# SX1276_e268v01a.net
KiCad netlist of a schematic drawn in Altium Designer
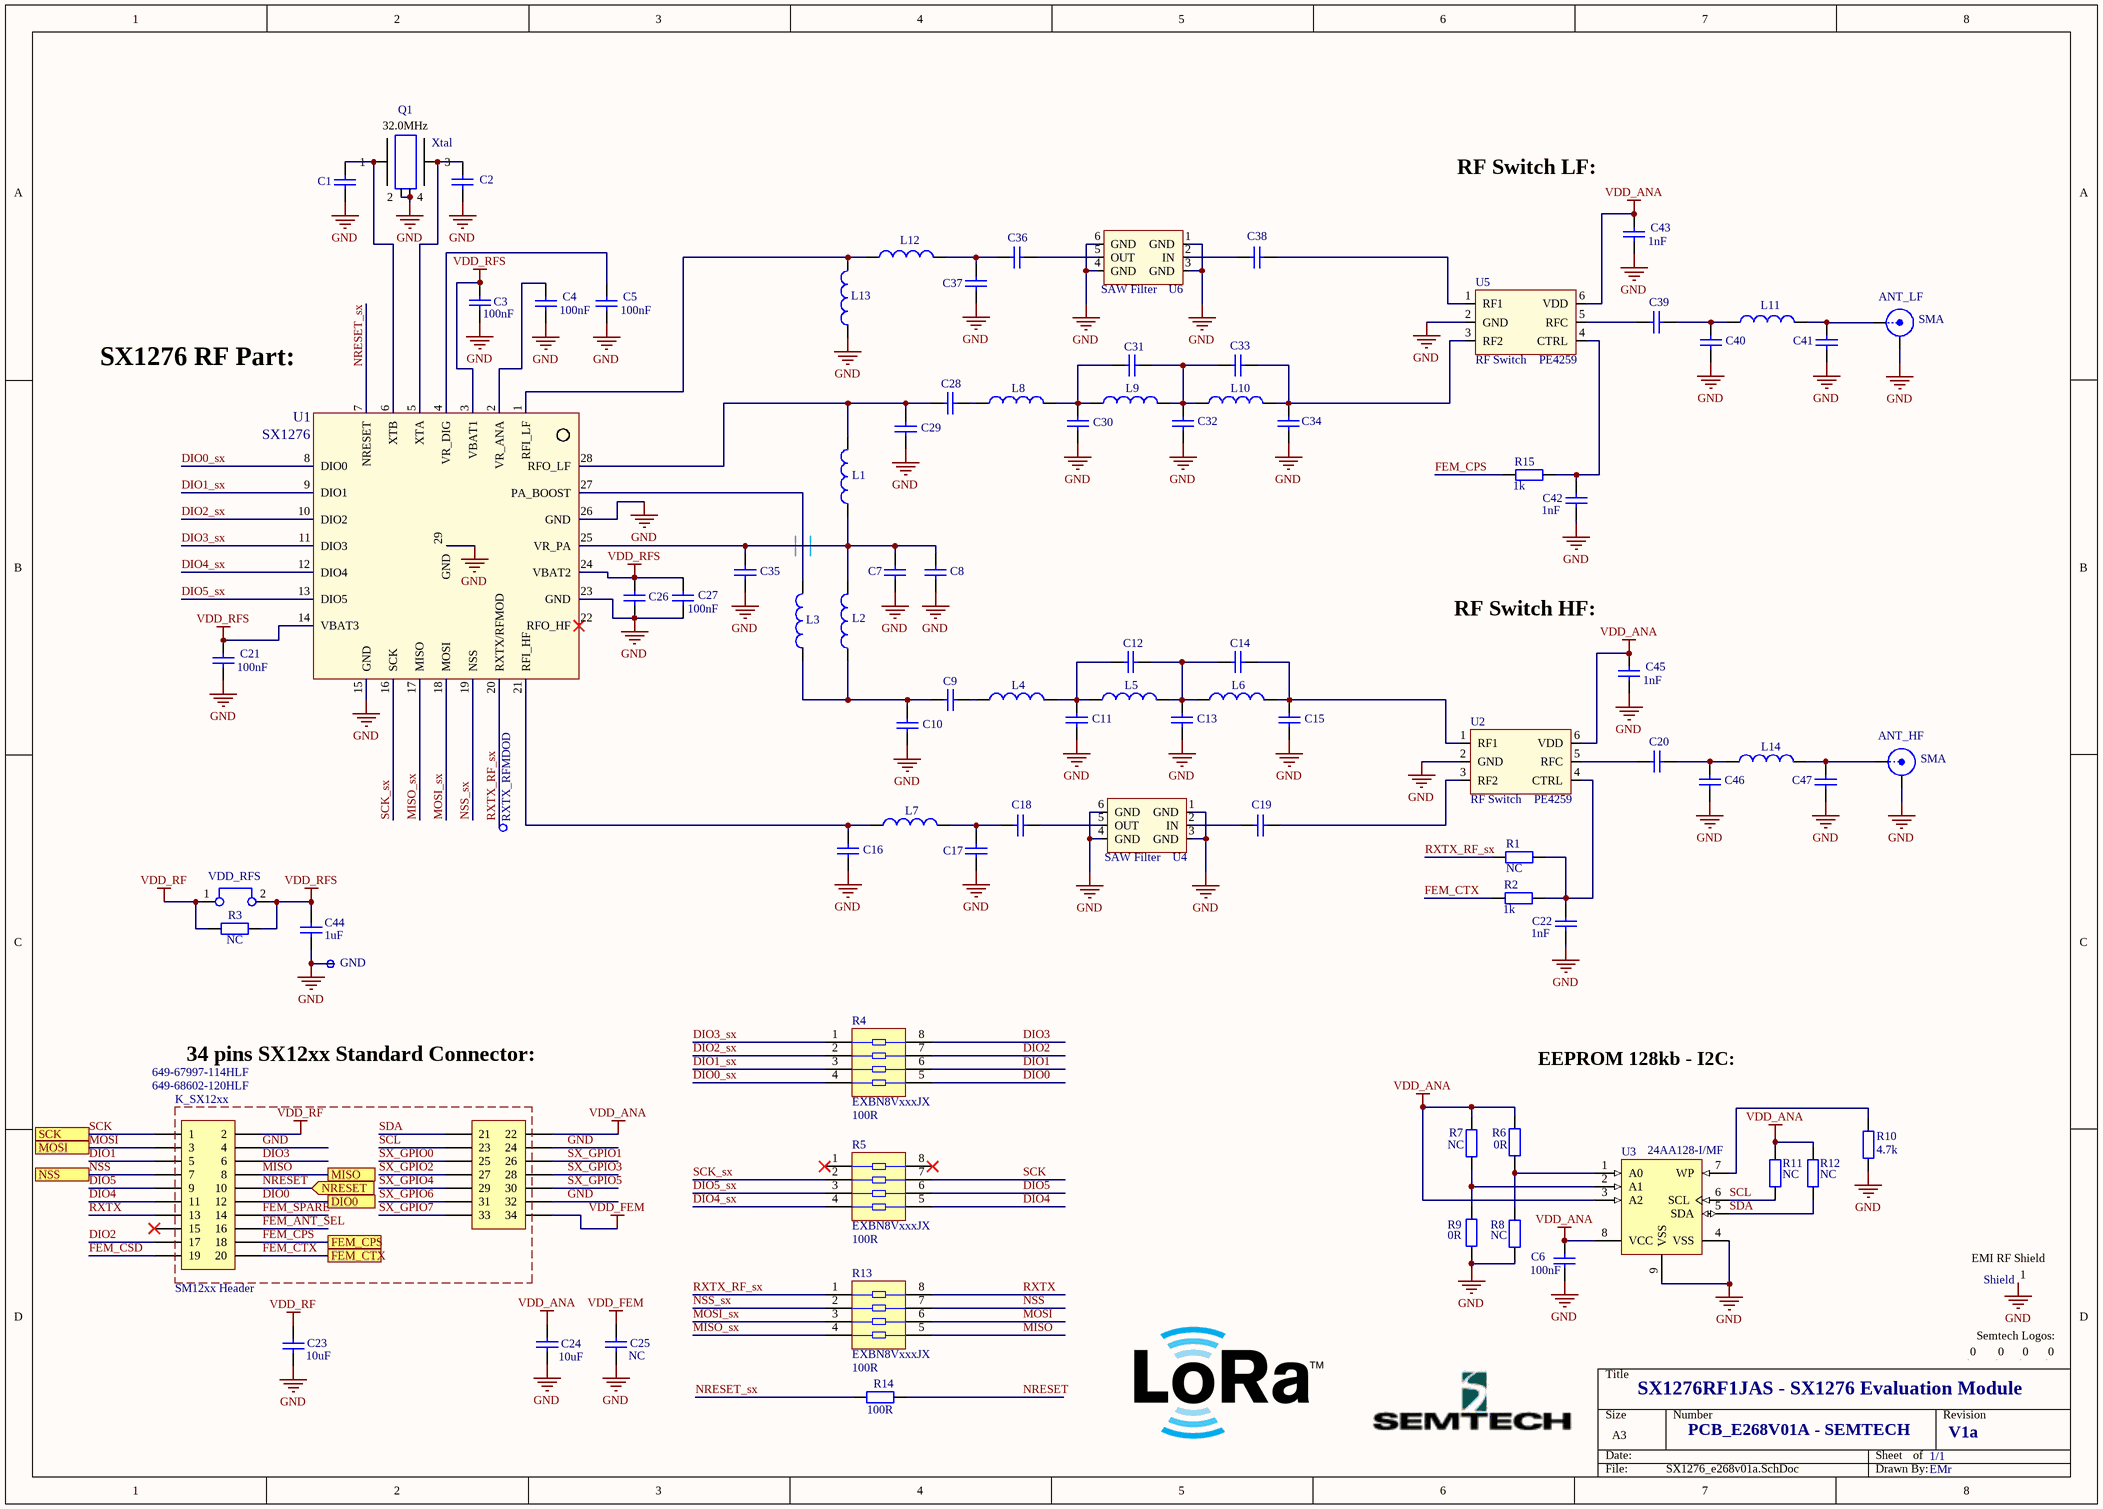
[diagram p0: SX1276_e268v01a.SchDoc]

(export (version "E")
  (design (tool "Eeschema 10.0.6"))
  (components
    (comp (ref "ANT_HF")
      (value "SMA")
      (footprint "SMA END LAUNCH JACK RECEPTACLE SHORT")
      (description "SMA Straight Connector")
      (fields (field (name "PUBLISHER") "Altium Limited"))
      (libsource (lib "SX1276_e268v01a") (part "SMA"))
    )
    (comp (ref "ANT_LF")
      (value "SMA")
      (footprint "SMA END LAUNCH JACK RECEPTACLE SHORT")
      (description "SMA Straight Connector")
      (fields (field (name "PUBLISHER") "Altium Limited"))
      (libsource (lib "SX1276_e268v01a") (part "SMA"))
    )
    (comp (ref "C1")
      (value "Cap")
      (footprint "rlc_402_smd")
      (description "Capacitor SMD")
      (fields (field (name "PUBLISHER") "Altium Limited"))
      (libsource (lib "SX1276_e268v01a") (part "Cap"))
    )
    (comp (ref "C2")
      (value "Cap")
      (footprint "rlc_402_smd")
      (description "Capacitor SMD")
      (fields (field (name "PUBLISHER") "Altium Limited"))
      (libsource (lib "SX1276_e268v01a") (part "Cap"))
    )
    (comp (ref "C3")
      (value "100nF")
      (footprint "rlc_402_smd")
      (description "Capacitor SMD")
      (fields (field (name "Comment") "Cap") (field (name "PUBLISHER") "Altium Limited"))
      (libsource (lib "SX1276_e268v01a") (part "Cap"))
    )
    (comp (ref "C4")
      (value "100nF")
      (footprint "rlc_402_smd")
      (description "Capacitor SMD")
      (fields (field (name "Comment") "Cap") (field (name "PUBLISHER") "Altium Limited"))
      (libsource (lib "SX1276_e268v01a") (part "Cap"))
    )
    (comp (ref "C5")
      (value "100nF")
      (footprint "rlc_402_smd")
      (description "Capacitor SMD")
      (fields (field (name "Comment") "Cap") (field (name "PUBLISHER") "Altium Limited"))
      (libsource (lib "SX1276_e268v01a") (part "Cap"))
    )
    (comp (ref "C6")
      (value "100nF")
      (footprint "rlc_402_smd")
      (description "Capacitor SMD")
      (fields (field (name "Comment") "Cap") (field (name "PUBLISHER") "Altium Limited"))
      (libsource (lib "SX1276_e268v01a") (part "Cap"))
    )
    (comp (ref "C7")
      (value "Cap")
      (footprint "rlc_402_smd")
      (description "Capacitor SMD")
      (fields (field (name "PUBLISHER") "Altium Limited"))
      (libsource (lib "SX1276_e268v01a") (part "Cap"))
    )
    (comp (ref "C8")
      (value "Cap")
      (footprint "rlc_402_smd")
      (description "Capacitor SMD")
      (fields (field (name "PUBLISHER") "Altium Limited"))
      (libsource (lib "SX1276_e268v01a") (part "Cap"))
    )
    (comp (ref "C9")
      (value "Cap")
      (footprint "rlc_402_smd")
      (description "Capacitor SMD")
      (fields (field (name "PUBLISHER") "Altium Limited"))
      (libsource (lib "SX1276_e268v01a") (part "Cap"))
    )
    (comp (ref "C10")
      (value "Cap")
      (footprint "rlc_402_smd")
      (description "Capacitor SMD")
      (fields (field (name "PUBLISHER") "Altium Limited"))
      (libsource (lib "SX1276_e268v01a") (part "Cap"))
    )
    (comp (ref "C11")
      (value "Cap")
      (footprint "rlc_402_smd")
      (description "Capacitor SMD")
      (fields (field (name "PUBLISHER") "Altium Limited"))
      (libsource (lib "SX1276_e268v01a") (part "Cap"))
    )
    (comp (ref "C12")
      (value "Cap")
      (footprint "rlc_402_smd")
      (description "Capacitor SMD")
      (fields (field (name "PUBLISHER") "Altium Limited"))
      (libsource (lib "SX1276_e268v01a") (part "Cap"))
    )
    (comp (ref "C13")
      (value "Cap")
      (footprint "rlc_402_smd")
      (description "Capacitor SMD")
      (fields (field (name "PUBLISHER") "Altium Limited"))
      (libsource (lib "SX1276_e268v01a") (part "Cap"))
    )
    (comp (ref "C14")
      (value "Cap")
      (footprint "rlc_402_smd")
      (description "Capacitor SMD")
      (fields (field (name "PUBLISHER") "Altium Limited"))
      (libsource (lib "SX1276_e268v01a") (part "Cap"))
    )
    (comp (ref "C15")
      (value "Cap")
      (footprint "rlc_402_smd")
      (description "Capacitor SMD")
      (fields (field (name "PUBLISHER") "Altium Limited"))
      (libsource (lib "SX1276_e268v01a") (part "Cap"))
    )
    (comp (ref "C16")
      (value "Cap")
      (footprint "rlc_402_smd")
      (description "Capacitor SMD")
      (fields (field (name "PUBLISHER") "Altium Limited"))
      (libsource (lib "SX1276_e268v01a") (part "Cap"))
    )
    (comp (ref "C17")
      (value "Cap")
      (footprint "rlc_402_smd")
      (description "Capacitor SMD")
      (fields (field (name "PUBLISHER") "Altium Limited"))
      (libsource (lib "SX1276_e268v01a") (part "Cap"))
    )
    (comp (ref "C18")
      (value "Cap")
      (footprint "rlc_402_smd")
      (description "Capacitor SMD")
      (fields (field (name "PUBLISHER") "Altium Limited"))
      (libsource (lib "SX1276_e268v01a") (part "Cap"))
    )
    (comp (ref "C19")
      (value "Cap")
      (footprint "rlc_402_smd")
      (description "Capacitor SMD")
      (fields (field (name "PUBLISHER") "Altium Limited"))
      (libsource (lib "SX1276_e268v01a") (part "Cap"))
    )
    (comp (ref "C20")
      (value "Cap")
      (footprint "rlc_402_smd")
      (description "Capacitor SMD")
      (fields (field (name "PUBLISHER") "Altium Limited"))
      (libsource (lib "SX1276_e268v01a") (part "Cap"))
    )
    (comp (ref "C21")
      (value "100nF")
      (footprint "rlc_402_smd")
      (description "Capacitor SMD")
      (fields (field (name "Comment") "Cap") (field (name "PUBLISHER") "Altium Limited"))
      (libsource (lib "SX1276_e268v01a") (part "Cap"))
    )
    (comp (ref "C22")
      (value "1nF")
      (footprint "rlc_402_smd")
      (description "Capacitor SMD")
      (fields (field (name "Comment") "Cap") (field (name "PUBLISHER") "Altium Limited"))
      (libsource (lib "SX1276_e268v01a") (part "Cap"))
    )
    (comp (ref "C23")
      (value "10uF")
      (footprint "rlc_805_smd")
      (description "Capacitor SMD")
      (fields (field (name "Comment") "Cap") (field (name "PUBLISHER") "Altium Limited"))
      (libsource (lib "SX1276_e268v01a") (part "Cap"))
    )
    (comp (ref "C24")
      (value "10uF")
      (footprint "rlc_805_smd")
      (description "Capacitor SMD")
      (fields (field (name "Comment") "Cap") (field (name "PUBLISHER") "Altium Limited"))
      (libsource (lib "SX1276_e268v01a") (part "Cap"))
    )
    (comp (ref "C25")
      (value "NC")
      (footprint "rlc_805_smd")
      (description "Capacitor SMD")
      (fields (field (name "Comment") "Cap") (field (name "PUBLISHER") "Altium Limited"))
      (libsource (lib "SX1276_e268v01a") (part "Cap"))
    )
    (comp (ref "C26")
      (value "Cap")
      (footprint "rlc_402_smd")
      (description "Capacitor SMD")
      (fields (field (name "PUBLISHER") "Altium Limited"))
      (libsource (lib "SX1276_e268v01a") (part "Cap"))
    )
    (comp (ref "C27")
      (value "100nF")
      (footprint "rlc_402_smd")
      (description "Capacitor SMD")
      (fields (field (name "Comment") "Cap") (field (name "PUBLISHER") "Altium Limited"))
      (libsource (lib "SX1276_e268v01a") (part "Cap"))
    )
    (comp (ref "C28")
      (value "Cap")
      (footprint "rlc_402_smd")
      (description "Capacitor SMD")
      (fields (field (name "PUBLISHER") "Altium Limited"))
      (libsource (lib "SX1276_e268v01a") (part "Cap"))
    )
    (comp (ref "C29")
      (value "Cap")
      (footprint "rlc_402_smd")
      (description "Capacitor SMD")
      (fields (field (name "PUBLISHER") "Altium Limited"))
      (libsource (lib "SX1276_e268v01a") (part "Cap"))
    )
    (comp (ref "C30")
      (value "Cap")
      (footprint "rlc_402_smd")
      (description "Capacitor SMD")
      (fields (field (name "PUBLISHER") "Altium Limited"))
      (libsource (lib "SX1276_e268v01a") (part "Cap"))
    )
    (comp (ref "C31")
      (value "Cap")
      (footprint "rlc_402_smd")
      (description "Capacitor SMD")
      (fields (field (name "PUBLISHER") "Altium Limited"))
      (libsource (lib "SX1276_e268v01a") (part "Cap"))
    )
    (comp (ref "C32")
      (value "Cap")
      (footprint "rlc_402_smd")
      (description "Capacitor SMD")
      (fields (field (name "PUBLISHER") "Altium Limited"))
      (libsource (lib "SX1276_e268v01a") (part "Cap"))
    )
    (comp (ref "C33")
      (value "Cap")
      (footprint "rlc_402_smd")
      (description "Capacitor SMD")
      (fields (field (name "PUBLISHER") "Altium Limited"))
      (libsource (lib "SX1276_e268v01a") (part "Cap"))
    )
    (comp (ref "C34")
      (value "Cap")
      (footprint "rlc_402_smd")
      (description "Capacitor SMD")
      (fields (field (name "PUBLISHER") "Altium Limited"))
      (libsource (lib "SX1276_e268v01a") (part "Cap"))
    )
    (comp (ref "C35")
      (value "Cap")
      (footprint "rlc_402_smd")
      (description "Capacitor SMD")
      (fields (field (name "PUBLISHER") "Altium Limited"))
      (libsource (lib "SX1276_e268v01a") (part "Cap"))
    )
    (comp (ref "C36")
      (value "Cap")
      (footprint "rlc_402_smd")
      (description "Capacitor SMD")
      (fields (field (name "PUBLISHER") "Altium Limited"))
      (libsource (lib "SX1276_e268v01a") (part "Cap"))
    )
    (comp (ref "C37")
      (value "Cap")
      (footprint "rlc_402_smd")
      (description "Capacitor SMD")
      (fields (field (name "PUBLISHER") "Altium Limited"))
      (libsource (lib "SX1276_e268v01a") (part "Cap"))
    )
    (comp (ref "C38")
      (value "Cap")
      (footprint "rlc_402_smd")
      (description "Capacitor SMD")
      (fields (field (name "PUBLISHER") "Altium Limited"))
      (libsource (lib "SX1276_e268v01a") (part "Cap"))
    )
    (comp (ref "C39")
      (value "Cap")
      (footprint "rlc_402_smd")
      (description "Capacitor SMD")
      (fields (field (name "PUBLISHER") "Altium Limited"))
      (libsource (lib "SX1276_e268v01a") (part "Cap"))
    )
    (comp (ref "C40")
      (value "Cap")
      (footprint "rlc_402_smd")
      (description "Capacitor SMD")
      (fields (field (name "PUBLISHER") "Altium Limited"))
      (libsource (lib "SX1276_e268v01a") (part "Cap"))
    )
    (comp (ref "C41")
      (value "Cap")
      (footprint "rlc_402_smd")
      (description "Capacitor SMD")
      (fields (field (name "PUBLISHER") "Altium Limited"))
      (libsource (lib "SX1276_e268v01a") (part "Cap"))
    )
    (comp (ref "C42")
      (value "1nF")
      (footprint "rlc_402_smd")
      (description "Capacitor SMD")
      (fields (field (name "Comment") "Cap") (field (name "PUBLISHER") "Altium Limited"))
      (libsource (lib "SX1276_e268v01a") (part "Cap"))
    )
    (comp (ref "C43")
      (value "1nF")
      (footprint "rlc_402_smd")
      (description "Capacitor SMD")
      (fields (field (name "Comment") "Cap") (field (name "PUBLISHER") "Altium Limited"))
      (libsource (lib "SX1276_e268v01a") (part "Cap"))
    )
    (comp (ref "C44")
      (value "1uF")
      (footprint "rlc_603_smd")
      (description "Capacitor (Semiconductor SIM Model)")
      (fields (field (name "Comment") "Cap Semi") (field (name "PUBLISHER") "Altium Limited"))
      (libsource (lib "SX1276_e268v01a") (part "Cap Semi"))
    )
    (comp (ref "C45")
      (value "1nF")
      (footprint "rlc_402_smd")
      (description "Capacitor SMD")
      (fields (field (name "Comment") "Cap") (field (name "PUBLISHER") "Altium Limited"))
      (libsource (lib "SX1276_e268v01a") (part "Cap"))
    )
    (comp (ref "C46")
      (value "Cap")
      (footprint "rlc_402_smd")
      (description "Capacitor SMD")
      (fields (field (name "PUBLISHER") "Altium Limited"))
      (libsource (lib "SX1276_e268v01a") (part "Cap"))
    )
    (comp (ref "C47")
      (value "Cap")
      (footprint "rlc_402_smd")
      (description "Capacitor SMD")
      (fields (field (name "PUBLISHER") "Altium Limited"))
      (libsource (lib "SX1276_e268v01a") (part "Cap"))
    )
    (comp (ref "GND")
      (value "Test Pin")
      (footprint "pin_1mm")
      (libsource (lib "SX1276_e268v01a") (part "test_pin"))
    )
    (comp (ref "K_SX12xx")
      (value "SM12xx Header")
      (footprint "HDR34 Header")
      (description "SM12xx Header; 34pins: 2x10pins + 2x7pins")
      (fields
        (field (name "SUPPLIER PART NUMBER 1") "649-68602-120HLF")
        (field (name "SUPPLIER PART NUMBER 2") "649-67997-114HLF")
        (field (name "PUBLISHER") "Altium Limited")
      )
      (libsource (lib "SX1276_e268v01a") (part "SM12xx Header"))
    )
    (comp (ref "L1")
      (value "Inductor")
      (footprint "rlc_402_smd")
      (description "Inductor SMD")
      (fields (field (name "PUBLISHER") "Altium Limited"))
      (libsource (lib "SX1276_e268v01a") (part "Inductor"))
    )
    (comp (ref "L2")
      (value "Inductor")
      (footprint "rlc_402_smd")
      (description "Inductor SMD")
      (fields (field (name "PUBLISHER") "Altium Limited"))
      (libsource (lib "SX1276_e268v01a") (part "Inductor"))
    )
    (comp (ref "L3")
      (value "Inductor")
      (footprint "rlc_402_smd")
      (description "Inductor SMD")
      (fields (field (name "PUBLISHER") "Altium Limited"))
      (libsource (lib "SX1276_e268v01a") (part "Inductor"))
    )
    (comp (ref "L4")
      (value "Inductor")
      (footprint "rlc_402_smd")
      (description "Inductor SMD")
      (fields (field (name "PUBLISHER") "Altium Limited"))
      (libsource (lib "SX1276_e268v01a") (part "Inductor"))
    )
    (comp (ref "L5")
      (value "Inductor")
      (footprint "rlc_402_smd")
      (description "Inductor SMD")
      (fields (field (name "PUBLISHER") "Altium Limited"))
      (libsource (lib "SX1276_e268v01a") (part "Inductor"))
    )
    (comp (ref "L6")
      (value "Inductor")
      (footprint "rlc_402_smd")
      (description "Inductor SMD")
      (fields (field (name "PUBLISHER") "Altium Limited"))
      (libsource (lib "SX1276_e268v01a") (part "Inductor"))
    )
    (comp (ref "L7")
      (value "Inductor")
      (footprint "rlc_402_smd")
      (description "Inductor SMD")
      (fields (field (name "PUBLISHER") "Altium Limited"))
      (libsource (lib "SX1276_e268v01a") (part "Inductor"))
    )
    (comp (ref "L8")
      (value "Inductor")
      (footprint "rlc_402_smd")
      (description "Inductor SMD")
      (fields (field (name "PUBLISHER") "Altium Limited"))
      (libsource (lib "SX1276_e268v01a") (part "Inductor"))
    )
    (comp (ref "L9")
      (value "Inductor")
      (footprint "rlc_402_smd")
      (description "Inductor SMD")
      (fields (field (name "PUBLISHER") "Altium Limited"))
      (libsource (lib "SX1276_e268v01a") (part "Inductor"))
    )
    (comp (ref "L10")
      (value "Inductor")
      (footprint "rlc_402_smd")
      (description "Inductor SMD")
      (fields (field (name "PUBLISHER") "Altium Limited"))
      (libsource (lib "SX1276_e268v01a") (part "Inductor"))
    )
    (comp (ref "L11")
      (value "Inductor")
      (footprint "rlc_402_smd")
      (description "Inductor SMD")
      (fields (field (name "PUBLISHER") "Altium Limited"))
      (libsource (lib "SX1276_e268v01a") (part "Inductor"))
    )
    (comp (ref "L12")
      (value "Inductor")
      (footprint "rlc_402_smd")
      (description "Inductor SMD")
      (fields (field (name "PUBLISHER") "Altium Limited"))
      (libsource (lib "SX1276_e268v01a") (part "Inductor"))
    )
    (comp (ref "L13")
      (value "Inductor")
      (footprint "rlc_402_smd")
      (description "Inductor SMD")
      (fields (field (name "PUBLISHER") "Altium Limited"))
      (libsource (lib "SX1276_e268v01a") (part "Inductor"))
    )
    (comp (ref "L14")
      (value "Inductor")
      (footprint "rlc_402_smd")
      (description "Inductor SMD")
      (fields (field (name "PUBLISHER") "Altium Limited"))
      (libsource (lib "SX1276_e268v01a") (part "Inductor"))
    )
    (comp (ref "Logo Bot")
      (value "Logo symbol")
      (footprint "logo_semtech_horiz_size3")
      (description "Schematic symbol for Logo")
      (libsource (lib "SX1276_e268v01a") (part "Logo"))
    )
    (comp (ref "Logo Lora Bot")
      (value "Logo symbol")
      (footprint "Logo LoRa Size4")
      (description "Schematic symbol for Logo")
      (libsource (lib "SX1276_e268v01a") (part "Logo"))
    )
    (comp (ref "Logo Lora Top")
      (value "Logo symbol")
      (footprint "Logo LoRa Size3")
      (description "Schematic symbol for Logo")
      (libsource (lib "SX1276_e268v01a") (part "Logo"))
    )
    (comp (ref "Logo Top")
      (value "Logo symbol")
      (footprint "logo_semtech_horiz_size2")
      (description "Schematic symbol for Logo")
      (libsource (lib "SX1276_e268v01a") (part "Logo"))
    )
    (comp (ref "Q1")
      (value "Xtal")
      (footprint "nd3225da - nd2520da")
      (description "Crystal with GND pins")
      (fields (field (name "ALTIUM_VALUE") "32.0MHz"))
      (libsource (lib "SX1276_e268v01a") (part "Xtal GND"))
    )
    (comp (ref "R1")
      (value "NC")
      (footprint "rlc_402_smd")
      (description "Resistor SMD - IEC symbol version")
      (fields (field (name "Comment") "Resistor"))
      (libsource (lib "") (part "Resistor_1"))
    )
    (comp (ref "R2")
      (value "1k")
      (footprint "rlc_402_smd")
      (description "Resistor SMD - IEC symbol version")
      (fields (field (name "Comment") "Resistor"))
      (libsource (lib "SX1276_e268v01a") (part "Resistor"))
    )
    (comp (ref "R3")
      (value "NC")
      (footprint "rlc_805_smd")
      (description "Resistor SMD - IEC symbol version")
      (fields (field (name "Comment") "Resistor"))
      (libsource (lib "SX1276_e268v01a") (part "Resistor"))
    )
    (comp (ref "R4")
      (value "EXBN8VxxxJX")
      (footprint "EXB28V")
      (description "Mini-Flat Package, Isolated Resistor Network, 0.031 W/resistor")
      (fields (field (name "ALTIUM_VALUE") "100R"))
      (libsource (lib "SX1276_e268v01a") (part "EXBN8VxxxJX"))
    )
    (comp (ref "R5")
      (value "EXBN8VxxxJX")
      (footprint "EXB28V")
      (description "Mini-Flat Package, Isolated Resistor Network, 0.031 W/resistor")
      (fields (field (name "ALTIUM_VALUE") "100R"))
      (libsource (lib "SX1276_e268v01a") (part "EXBN8VxxxJX"))
    )
    (comp (ref "R6")
      (value "0R")
      (footprint "rlc_402_smd")
      (description "Resistor SMD - IEC symbol version")
      (fields (field (name "Comment") "Resistor"))
      (libsource (lib "") (part "Resistor_1"))
    )
    (comp (ref "R7")
      (value "NC")
      (footprint "rlc_402_smd")
      (description "Resistor SMD - IEC symbol version")
      (fields (field (name "Comment") "Resistor"))
      (libsource (lib "") (part "Resistor_1"))
    )
    (comp (ref "R8")
      (value "NC")
      (footprint "rlc_402_smd")
      (description "Resistor SMD - IEC symbol version")
      (fields (field (name "Comment") "Resistor"))
      (libsource (lib "") (part "Resistor_1"))
    )
    (comp (ref "R9")
      (value "0R")
      (footprint "rlc_402_smd")
      (description "Resistor SMD - IEC symbol version")
      (fields (field (name "Comment") "Resistor"))
      (libsource (lib "") (part "Resistor_1"))
    )
    (comp (ref "R10")
      (value "4.7k")
      (footprint "rlc_402_smd")
      (description "Resistor SMD - IEC symbol version")
      (fields (field (name "Comment") "Resistor"))
      (libsource (lib "") (part "Resistor_1"))
    )
    (comp (ref "R11")
      (value "NC")
      (footprint "rlc_402_smd")
      (description "Resistor SMD - IEC symbol version")
      (fields (field (name "Comment") "Resistor"))
      (libsource (lib "") (part "Resistor_1"))
    )
    (comp (ref "R12")
      (value "NC")
      (footprint "rlc_402_smd")
      (description "Resistor SMD - IEC symbol version")
      (fields (field (name "Comment") "Resistor"))
      (libsource (lib "") (part "Resistor_1"))
    )
    (comp (ref "R13")
      (value "EXBN8VxxxJX")
      (footprint "EXB28V")
      (description "Mini-Flat Package, Isolated Resistor Network, 0.031 W/resistor")
      (fields (field (name "ALTIUM_VALUE") "100R"))
      (libsource (lib "SX1276_e268v01a") (part "EXBN8VxxxJX"))
    )
    (comp (ref "R14")
      (value "100R")
      (footprint "rlc_402_smd")
      (description "Resistor SMD - IEC symbol version")
      (fields (field (name "Comment") "Resistor"))
      (libsource (lib "") (part "Resistor_2"))
    )
    (comp (ref "R15")
      (value "1k")
      (footprint "rlc_402_smd")
      (description "Resistor SMD - IEC symbol version")
      (fields (field (name "Comment") "Resistor"))
      (libsource (lib "SX1276_e268v01a") (part "Resistor"))
    )
    (comp (ref "RXTX_RFMDOD")
      (value "Test Pin")
      (footprint "pin_SMD")
      (libsource (lib "SX1276_e268v01a") (part "test_pin"))
    )
    (comp (ref "Shield")
      (value "Logo symbol")
      (footprint "BMIS-205-F - Shield")
      (description "Shield - EMI Gasket - Standard Surface Mount Shields")
      (libsource (lib "SX1276_e268v01a") (part "Shield"))
    )
    (comp (ref "U1")
      (value "SX1276")
      (footprint "vqfn28_6x6mm")
      (description "SX1276 - Low Power Integrated UHF Transceiver with loRa Modem")
      (libsource (lib "SX1276_e268v01a") (part "SX1276"))
    )
    (comp (ref "U2")
      (value "RF Switch")
      (footprint "SC70-6")
      (description "PE4259 Peregrine RF Switch")
      (fields (field (name "ALTIUM_VALUE") "PE4259"))
      (libsource (lib "SX1276_e268v01a") (part "PE4259 RF Switch"))
    )
    (comp (ref "U3")
      (value "24AA128-I/MF")
      (footprint "DFN8_ 5x6mm")
      (description "128kbit, 400kHz, 1.7V, 8-Pin DFN, Industrial Temperature")
      (fields (field (name "PUBLISHER") "Altium Limited"))
      (libsource (lib "SX1276_e268v01a") (part "24AA128-I/MF"))
    )
    (comp (ref "U4")
      (value "SAW Filter")
      (footprint "DCC6C_3.0x3.0mm")
      (description "SAW Filter - Bandpass - TEMEX type")
      (libsource (lib "SX1276_e268v01a") (part "SAW Filter"))
    )
    (comp (ref "U5")
      (value "RF Switch")
      (footprint "SC70-6")
      (description "PE4259 Peregrine RF Switch")
      (fields (field (name "ALTIUM_VALUE") "PE4259"))
      (libsource (lib "SX1276_e268v01a") (part "PE4259 RF Switch"))
    )
    (comp (ref "U6")
      (value "SAW Filter")
      (footprint "DCC6C_3.0x3.0mm")
      (description "SAW Filter - Bandpass - TEMEX type")
      (libsource (lib "SX1276_e268v01a") (part "SAW Filter"))
    )
    (comp (ref "VDD_RFS")
      (value "Jumper")
      (footprint "bridge_254mm")
      (description "Jumper Wire")
      (libsource (lib "SX1276_e268v01a") (part "Jumper"))
    )
  )
  (nets
    (net (code "1") (name "/DIO0") (class "Default")
      (node (ref "K_SX12xx") (pin "12") (pinfunction "12_12") (pintype "passive"))
      (node (ref "R4") (pin "5") (pinfunction "5_5") (pintype "passive"))
    )
    (net (code "2") (name "/DIO0_sx") (class "Default")
      (node (ref "R4") (pin "4") (pinfunction "4_4") (pintype "passive"))
      (node (ref "U1") (pin "8") (pinfunction "DIO0_8") (pintype "passive"))
    )
    (net (code "3") (name "/DIO1") (class "Default")
      (node (ref "K_SX12xx") (pin "5") (pinfunction "5_5") (pintype "passive"))
      (node (ref "R4") (pin "6") (pinfunction "6_6") (pintype "passive"))
    )
    (net (code "4") (name "/DIO1_sx") (class "Default")
      (node (ref "R4") (pin "3") (pinfunction "3_3") (pintype "passive"))
      (node (ref "U1") (pin "9") (pinfunction "DIO1_9") (pintype "passive"))
    )
    (net (code "5") (name "/DIO2") (class "Default")
      (node (ref "K_SX12xx") (pin "17") (pinfunction "17_17") (pintype "passive"))
      (node (ref "R4") (pin "7") (pinfunction "7_7") (pintype "passive"))
    )
    (net (code "6") (name "/DIO2_sx") (class "Default")
      (node (ref "R4") (pin "2") (pinfunction "2_2") (pintype "passive"))
      (node (ref "U1") (pin "10") (pinfunction "DIO2_10") (pintype "passive"))
    )
    (net (code "7") (name "/DIO3") (class "Default")
      (node (ref "K_SX12xx") (pin "6") (pinfunction "6_6") (pintype "passive"))
      (node (ref "R4") (pin "8") (pinfunction "8_8") (pintype "passive"))
    )
    (net (code "8") (name "/DIO3_sx") (class "Default")
      (node (ref "R4") (pin "1") (pinfunction "1_1") (pintype "passive"))
      (node (ref "U1") (pin "11") (pinfunction "DIO3_11") (pintype "passive"))
    )
    (net (code "9") (name "/DIO4") (class "Default")
      (node (ref "K_SX12xx") (pin "11") (pinfunction "11_11") (pintype "passive"))
      (node (ref "R5") (pin "5") (pinfunction "5_5") (pintype "passive"))
    )
    (net (code "10") (name "/DIO4_sx") (class "Default")
      (node (ref "R5") (pin "4") (pinfunction "4_4") (pintype "passive"))
      (node (ref "U1") (pin "12") (pinfunction "DIO4_12") (pintype "passive"))
    )
    (net (code "11") (name "/DIO5") (class "Default")
      (node (ref "K_SX12xx") (pin "9") (pinfunction "9_9") (pintype "passive"))
      (node (ref "R5") (pin "6") (pinfunction "6_6") (pintype "passive"))
    )
    (net (code "12") (name "/DIO5_sx") (class "Default")
      (node (ref "R5") (pin "3") (pinfunction "3_3") (pintype "passive"))
      (node (ref "U1") (pin "13") (pinfunction "DIO5_13") (pintype "passive"))
    )
    (net (code "13") (name "/FEM_ANT_SEL") (class "Default")
      (node (ref "K_SX12xx") (pin "16") (pinfunction "16_16") (pintype "passive"))
    )
    (net (code "14") (name "/FEM_CPS") (class "Default")
      (node (ref "K_SX12xx") (pin "18") (pinfunction "18_18") (pintype "passive"))
      (node (ref "R15") (pin "2") (pinfunction "2_2") (pintype "passive"))
    )
    (net (code "15") (name "/FEM_CSD") (class "Default")
      (node (ref "K_SX12xx") (pin "19") (pinfunction "19_19") (pintype "passive"))
    )
    (net (code "16") (name "/FEM_CTX") (class "Default")
      (node (ref "K_SX12xx") (pin "20") (pinfunction "20_20") (pintype "passive"))
      (node (ref "R2") (pin "2") (pinfunction "2_2") (pintype "passive"))
    )
    (net (code "17") (name "/FEM_SPARE") (class "Default")
      (node (ref "K_SX12xx") (pin "14") (pinfunction "14_14") (pintype "passive"))
    )
    (net (code "18") (name "/MISO") (class "Default")
      (node (ref "K_SX12xx") (pin "8") (pinfunction "8_8") (pintype "passive"))
      (node (ref "R13") (pin "5") (pinfunction "5_5") (pintype "passive"))
    )
    (net (code "19") (name "/MISO_sx") (class "Default")
      (node (ref "R13") (pin "4") (pinfunction "4_4") (pintype "passive"))
      (node (ref "U1") (pin "17") (pinfunction "MISO_17") (pintype "passive"))
    )
    (net (code "20") (name "/MOSI") (class "Default")
      (node (ref "K_SX12xx") (pin "3") (pinfunction "3_3") (pintype "passive"))
      (node (ref "R13") (pin "6") (pinfunction "6_6") (pintype "passive"))
    )
    (net (code "21") (name "/MOSI_sx") (class "Default")
      (node (ref "R13") (pin "3") (pinfunction "3_3") (pintype "passive"))
      (node (ref "U1") (pin "18") (pinfunction "MOSI_18") (pintype "passive"))
    )
    (net (code "22") (name "/NRESET") (class "Default")
      (node (ref "K_SX12xx") (pin "10") (pinfunction "10_10") (pintype "passive"))
      (node (ref "R14") (pin "2") (pinfunction "2_2") (pintype "passive"))
    )
    (net (code "23") (name "/NRESET_sx") (class "Default")
      (node (ref "R14") (pin "1") (pinfunction "1_1") (pintype "passive"))
      (node (ref "U1") (pin "7") (pinfunction "NRESET_7") (pintype "passive"))
    )
    (net (code "24") (name "/NSS") (class "Default")
      (node (ref "K_SX12xx") (pin "7") (pinfunction "7_7") (pintype "passive"))
      (node (ref "R13") (pin "7") (pinfunction "7_7") (pintype "passive"))
    )
    (net (code "25") (name "/NSS_sx") (class "Default")
      (node (ref "R13") (pin "2") (pinfunction "2_2") (pintype "passive"))
      (node (ref "U1") (pin "19") (pinfunction "NSS_19") (pintype "passive"))
    )
    (net (code "26") (name "/RXTX") (class "Default")
      (node (ref "K_SX12xx") (pin "13") (pinfunction "13_13") (pintype "passive"))
      (node (ref "R13") (pin "8") (pinfunction "8_8") (pintype "passive"))
    )
    (net (code "27") (name "/RXTX_RF_sx") (class "Default")
      (node (ref "R1") (pin "1") (pinfunction "1_1") (pintype "passive"))
      (node (ref "R13") (pin "1") (pinfunction "1_1") (pintype "passive"))
      (node (ref "RXTX_RFMDOD") (pin "1") (pinfunction "pin_1") (pintype "passive"))
      (node (ref "U1") (pin "20") (pinfunction "RXTX/RFMOD_20") (pintype "passive"))
    )
    (net (code "28") (name "/SCK") (class "Default")
      (node (ref "K_SX12xx") (pin "1") (pinfunction "1_1") (pintype "passive"))
      (node (ref "R5") (pin "7") (pinfunction "7_7") (pintype "passive"))
    )
    (net (code "29") (name "/SCK_sx") (class "Default")
      (node (ref "R5") (pin "2") (pinfunction "2_2") (pintype "passive"))
      (node (ref "U1") (pin "16") (pinfunction "SCK_16") (pintype "passive"))
    )
    (net (code "30") (name "/SCL") (class "Default")
      (node (ref "K_SX12xx") (pin "23") (pinfunction "23_23") (pintype "passive"))
      (node (ref "R11") (pin "1") (pinfunction "1_1") (pintype "passive"))
      (node (ref "U3") (pin "6") (pinfunction "SCL_6") (pintype "input"))
    )
    (net (code "31") (name "/SDA") (class "Default")
      (node (ref "K_SX12xx") (pin "21") (pinfunction "21_21") (pintype "passive"))
      (node (ref "R12") (pin "1") (pinfunction "1_1") (pintype "passive"))
      (node (ref "U3") (pin "5") (pinfunction "SDA_5") (pintype "bidirectional"))
    )
    (net (code "32") (name "/SX_GPIO0") (class "Default")
      (node (ref "K_SX12xx") (pin "25") (pinfunction "25_25") (pintype "passive"))
    )
    (net (code "33") (name "/SX_GPIO1") (class "Default")
      (node (ref "K_SX12xx") (pin "26") (pinfunction "26_26") (pintype "passive"))
    )
    (net (code "34") (name "/SX_GPIO2") (class "Default")
      (node (ref "K_SX12xx") (pin "27") (pinfunction "27_27") (pintype "passive"))
    )
    (net (code "35") (name "/SX_GPIO3") (class "Default")
      (node (ref "K_SX12xx") (pin "28") (pinfunction "28_28") (pintype "passive"))
    )
    (net (code "36") (name "/SX_GPIO4") (class "Default")
      (node (ref "K_SX12xx") (pin "29") (pinfunction "29_29") (pintype "passive"))
    )
    (net (code "37") (name "/SX_GPIO5") (class "Default")
      (node (ref "K_SX12xx") (pin "30") (pinfunction "30_30") (pintype "passive"))
    )
    (net (code "38") (name "/SX_GPIO6") (class "Default")
      (node (ref "K_SX12xx") (pin "31") (pinfunction "31_31") (pintype "passive"))
    )
    (net (code "39") (name "/SX_GPIO7") (class "Default")
      (node (ref "K_SX12xx") (pin "33") (pinfunction "33_33") (pintype "passive"))
    )
    (net (code "40") (name "GND") (class "Default")
      (node (ref "ANT_HF") (pin "2") (pinfunction "GND_2") (pintype "passive"))
      (node (ref "ANT_LF") (pin "2") (pinfunction "GND_2") (pintype "passive"))
      (node (ref "C1") (pin "1") (pinfunction "1_1") (pintype "passive"))
      (node (ref "C10") (pin "1") (pinfunction "1_1") (pintype "passive"))
      (node (ref "C11") (pin "1") (pinfunction "1_1") (pintype "passive"))
      (node (ref "C13") (pin "1") (pinfunction "1_1") (pintype "passive"))
      (node (ref "C15") (pin "1") (pinfunction "1_1") (pintype "passive"))
      (node (ref "C16") (pin "1") (pinfunction "1_1") (pintype "passive"))
      (node (ref "C17") (pin "1") (pinfunction "1_1") (pintype "passive"))
      (node (ref "C2") (pin "1") (pinfunction "1_1") (pintype "passive"))
      (node (ref "C21") (pin "1") (pinfunction "1_1") (pintype "passive"))
      (node (ref "C22") (pin "2") (pinfunction "2_2") (pintype "passive"))
      (node (ref "C23") (pin "1") (pinfunction "1_1") (pintype "passive"))
      (node (ref "C24") (pin "1") (pinfunction "1_1") (pintype "passive"))
      (node (ref "C25") (pin "2") (pinfunction "2_2") (pintype "passive"))
      (node (ref "C26") (pin "1") (pinfunction "1_1") (pintype "passive"))
      (node (ref "C27") (pin "1") (pinfunction "1_1") (pintype "passive"))
      (node (ref "C29") (pin "1") (pinfunction "1_1") (pintype "passive"))
      (node (ref "C3") (pin "1") (pinfunction "1_1") (pintype "passive"))
      (node (ref "C30") (pin "1") (pinfunction "1_1") (pintype "passive"))
      (node (ref "C32") (pin "1") (pinfunction "1_1") (pintype "passive"))
      (node (ref "C34") (pin "1") (pinfunction "1_1") (pintype "passive"))
      (node (ref "C35") (pin "1") (pinfunction "1_1") (pintype "passive"))
      (node (ref "C37") (pin "1") (pinfunction "1_1") (pintype "passive"))
      (node (ref "C4") (pin "1") (pinfunction "1_1") (pintype "passive"))
      (node (ref "C40") (pin "1") (pinfunction "1_1") (pintype "passive"))
      (node (ref "C41") (pin "1") (pinfunction "1_1") (pintype "passive"))
      (node (ref "C42") (pin "2") (pinfunction "2_2") (pintype "passive"))
      (node (ref "C43") (pin "1") (pinfunction "1_1") (pintype "passive"))
      (node (ref "C44") (pin "1") (pinfunction "1_1") (pintype "passive"))
      (node (ref "C45") (pin "1") (pinfunction "1_1") (pintype "passive"))
      (node (ref "C46") (pin "1") (pinfunction "1_1") (pintype "passive"))
      (node (ref "C47") (pin "1") (pinfunction "1_1") (pintype "passive"))
      (node (ref "C5") (pin "1") (pinfunction "1_1") (pintype "passive"))
      (node (ref "C6") (pin "1") (pinfunction "1_1") (pintype "passive"))
      (node (ref "C7") (pin "1") (pinfunction "1_1") (pintype "passive"))
      (node (ref "C8") (pin "1") (pinfunction "1_1") (pintype "passive"))
      (node (ref "GND") (pin "1") (pinfunction "pin_1") (pintype "passive"))
      (node (ref "K_SX12xx") (pin "24") (pinfunction "24_24") (pintype "passive"))
      (node (ref "K_SX12xx") (pin "32") (pinfunction "32_32") (pintype "passive"))
      (node (ref "K_SX12xx") (pin "4") (pinfunction "4_4") (pintype "passive"))
      (node (ref "L13") (pin "1") (pinfunction "1_1") (pintype "passive"))
      (node (ref "Q1") (pin "2") (pinfunction "2_2") (pintype "passive"))
      (node (ref "Q1") (pin "4") (pinfunction "4_4") (pintype "passive"))
      (node (ref "R10") (pin "1") (pinfunction "1_1") (pintype "passive"))
      (node (ref "R8") (pin "1") (pinfunction "1_1") (pintype "passive"))
      (node (ref "R9") (pin "1") (pinfunction "1_1") (pintype "passive"))
      (node (ref "Shield") (pin "1") (pinfunction "1_1") (pintype "passive"))
      (node (ref "U1") (pin "15") (pinfunction "GND_15") (pintype "passive"))
      (node (ref "U1") (pin "23") (pinfunction "GND_23") (pintype "passive"))
      (node (ref "U1") (pin "26") (pinfunction "GND_26") (pintype "passive"))
      (node (ref "U1") (pin "29") (pinfunction "GND_29") (pintype "passive"))
      (node (ref "U2") (pin "2") (pinfunction "GND_2") (pintype "passive"))
      (node (ref "U3") (pin "4") (pinfunction "VSS_4") (pintype "power_in"))
      (node (ref "U3") (pin "9") (pinfunction "VSS_9") (pintype "power_in"))
      (node (ref "U4") (pin "1") (pinfunction "GND_1") (pintype "passive"))
      (node (ref "U4") (pin "3") (pinfunction "GND_3") (pintype "passive"))
      (node (ref "U4") (pin "4") (pinfunction "GND_4") (pintype "passive"))
      (node (ref "U4") (pin "6") (pinfunction "GND_6") (pintype "passive"))
      (node (ref "U5") (pin "2") (pinfunction "GND_2") (pintype "passive"))
      (node (ref "U6") (pin "1") (pinfunction "GND_1") (pintype "passive"))
      (node (ref "U6") (pin "3") (pinfunction "GND_3") (pintype "passive"))
      (node (ref "U6") (pin "4") (pinfunction "GND_4") (pintype "passive"))
      (node (ref "U6") (pin "6") (pinfunction "GND_6") (pintype "passive"))
    )
    (net (code "41") (name "Net-(ANT_HF-Signal)") (class "Default")
      (node (ref "ANT_HF") (pin "1") (pinfunction "Signal_1") (pintype "passive"))
      (node (ref "C47") (pin "2") (pinfunction "2_2") (pintype "passive"))
      (node (ref "L14") (pin "2") (pinfunction "2_2") (pintype "passive"))
    )
    (net (code "42") (name "Net-(ANT_LF-Signal)") (class "Default")
      (node (ref "ANT_LF") (pin "1") (pinfunction "Signal_1") (pintype "passive"))
      (node (ref "C41") (pin "2") (pinfunction "2_2") (pintype "passive"))
      (node (ref "L11") (pin "2") (pinfunction "2_2") (pintype "passive"))
    )
    (net (code "43") (name "Net-(C9-Pad1)") (class "Default")
      (node (ref "C9") (pin "1") (pinfunction "1_1") (pintype "passive"))
      (node (ref "L4") (pin "1") (pinfunction "1_1") (pintype "passive"))
    )
    (net (code "44") (name "Net-(C10-Pad2)") (class "Default")
      (node (ref "C10") (pin "2") (pinfunction "2_2") (pintype "passive"))
      (node (ref "C9") (pin "2") (pinfunction "2_2") (pintype "passive"))
      (node (ref "L2") (pin "1") (pinfunction "1_1") (pintype "passive"))
      (node (ref "L3") (pin "1") (pinfunction "1_1") (pintype "passive"))
    )
    (net (code "45") (name "Net-(C11-Pad2)") (class "Default")
      (node (ref "C11") (pin "2") (pinfunction "2_2") (pintype "passive"))
      (node (ref "C12") (pin "2") (pinfunction "2_2") (pintype "passive"))
      (node (ref "L4") (pin "2") (pinfunction "2_2") (pintype "passive"))
      (node (ref "L5") (pin "1") (pinfunction "1_1") (pintype "passive"))
    )
    (net (code "46") (name "Net-(C12-Pad1)") (class "Default")
      (node (ref "C12") (pin "1") (pinfunction "1_1") (pintype "passive"))
      (node (ref "C13") (pin "2") (pinfunction "2_2") (pintype "passive"))
      (node (ref "C14") (pin "2") (pinfunction "2_2") (pintype "passive"))
      (node (ref "L5") (pin "2") (pinfunction "2_2") (pintype "passive"))
      (node (ref "L6") (pin "1") (pinfunction "1_1") (pintype "passive"))
    )
    (net (code "47") (name "Net-(C17-Pad2)") (class "Default")
      (node (ref "C17") (pin "2") (pinfunction "2_2") (pintype "passive"))
      (node (ref "C18") (pin "2") (pinfunction "2_2") (pintype "passive"))
      (node (ref "L7") (pin "2") (pinfunction "2_2") (pintype "passive"))
    )
    (net (code "48") (name "Net-(C20-Pad1)") (class "Default")
      (node (ref "C20") (pin "1") (pinfunction "1_1") (pintype "passive"))
      (node (ref "C46") (pin "2") (pinfunction "2_2") (pintype "passive"))
      (node (ref "L14") (pin "1") (pinfunction "1_1") (pintype "passive"))
    )
    (net (code "49") (name "Net-(C28-Pad1)") (class "Default")
      (node (ref "C28") (pin "1") (pinfunction "1_1") (pintype "passive"))
      (node (ref "L8") (pin "1") (pinfunction "1_1") (pintype "passive"))
    )
    (net (code "50") (name "Net-(C30-Pad2)") (class "Default")
      (node (ref "C30") (pin "2") (pinfunction "2_2") (pintype "passive"))
      (node (ref "C31") (pin "2") (pinfunction "2_2") (pintype "passive"))
      (node (ref "L8") (pin "2") (pinfunction "2_2") (pintype "passive"))
      (node (ref "L9") (pin "1") (pinfunction "1_1") (pintype "passive"))
    )
    (net (code "51") (name "Net-(C31-Pad1)") (class "Default")
      (node (ref "C31") (pin "1") (pinfunction "1_1") (pintype "passive"))
      (node (ref "C32") (pin "2") (pinfunction "2_2") (pintype "passive"))
      (node (ref "C33") (pin "2") (pinfunction "2_2") (pintype "passive"))
      (node (ref "L10") (pin "1") (pinfunction "1_1") (pintype "passive"))
      (node (ref "L9") (pin "2") (pinfunction "2_2") (pintype "passive"))
    )
    (net (code "52") (name "Net-(C36-Pad2)") (class "Default")
      (node (ref "C36") (pin "2") (pinfunction "2_2") (pintype "passive"))
      (node (ref "C37") (pin "2") (pinfunction "2_2") (pintype "passive"))
      (node (ref "L12") (pin "2") (pinfunction "2_2") (pintype "passive"))
    )
    (net (code "53") (name "Net-(C39-Pad1)") (class "Default")
      (node (ref "C39") (pin "1") (pinfunction "1_1") (pintype "passive"))
      (node (ref "C40") (pin "2") (pinfunction "2_2") (pintype "passive"))
      (node (ref "L11") (pin "1") (pinfunction "1_1") (pintype "passive"))
    )
    (net (code "54") (name "Net-(U1-PA_BOOST)") (class "Default")
      (node (ref "L3") (pin "2") (pinfunction "2_2") (pintype "passive"))
      (node (ref "U1") (pin "27") (pinfunction "PA_BOOST_27") (pintype "passive"))
    )
    (net (code "55") (name "Net-(U1-RFI_HF)") (class "Default")
      (node (ref "C16") (pin "2") (pinfunction "2_2") (pintype "passive"))
      (node (ref "L7") (pin "1") (pinfunction "1_1") (pintype "passive"))
      (node (ref "U1") (pin "21") (pinfunction "RFI_HF_21") (pintype "passive"))
    )
    (net (code "56") (name "Net-(U1-RFI_LF)") (class "Default")
      (node (ref "L12") (pin "1") (pinfunction "1_1") (pintype "passive"))
      (node (ref "L13") (pin "2") (pinfunction "2_2") (pintype "passive"))
      (node (ref "U1") (pin "1") (pinfunction "RFI_LF_1") (pintype "passive"))
    )
    (net (code "57") (name "Net-(U1-RFO_LF)") (class "Default")
      (node (ref "C28") (pin "2") (pinfunction "2_2") (pintype "passive"))
      (node (ref "C29") (pin "2") (pinfunction "2_2") (pintype "passive"))
      (node (ref "L1") (pin "2") (pinfunction "2_2") (pintype "passive"))
      (node (ref "U1") (pin "28") (pinfunction "RFO_LF_28") (pintype "passive"))
    )
    (net (code "58") (name "Net-(U1-VR_ANA)") (class "Default")
      (node (ref "C4") (pin "2") (pinfunction "2_2") (pintype "passive"))
      (node (ref "U1") (pin "2") (pinfunction "VR_ANA_2") (pintype "passive"))
    )
    (net (code "59") (name "Net-(U1-VR_DIG)") (class "Default")
      (node (ref "C5") (pin "2") (pinfunction "2_2") (pintype "passive"))
      (node (ref "U1") (pin "4") (pinfunction "VR_DIG_4") (pintype "passive"))
    )
    (net (code "60") (name "Net-(U1-VR_PA)") (class "Default")
      (node (ref "C35") (pin "2") (pinfunction "2_2") (pintype "passive"))
      (node (ref "C7") (pin "2") (pinfunction "2_2") (pintype "passive"))
      (node (ref "C8") (pin "2") (pinfunction "2_2") (pintype "passive"))
      (node (ref "L1") (pin "1") (pinfunction "1_1") (pintype "passive"))
      (node (ref "L2") (pin "2") (pinfunction "2_2") (pintype "passive"))
      (node (ref "U1") (pin "25") (pinfunction "VR_PA_25") (pintype "passive"))
    )
    (net (code "61") (name "Net-(U1-XTA)") (class "Default")
      (node (ref "C2") (pin "2") (pinfunction "2_2") (pintype "passive"))
      (node (ref "Q1") (pin "3") (pinfunction "3_3") (pintype "passive"))
      (node (ref "U1") (pin "5") (pinfunction "XTA_5") (pintype "passive"))
    )
    (net (code "62") (name "Net-(U1-XTB)") (class "Default")
      (node (ref "C1") (pin "2") (pinfunction "2_2") (pintype "passive"))
      (node (ref "Q1") (pin "1") (pinfunction "1_1") (pintype "passive"))
      (node (ref "U1") (pin "6") (pinfunction "XTB_6") (pintype "passive"))
    )
    (net (code "63") (name "Net-(U2-CTRL)") (class "Default")
      (node (ref "C22") (pin "1") (pinfunction "1_1") (pintype "passive"))
      (node (ref "R1") (pin "2") (pinfunction "2_2") (pintype "passive"))
      (node (ref "R2") (pin "1") (pinfunction "1_1") (pintype "passive"))
      (node (ref "U2") (pin "4") (pinfunction "CTRL_4") (pintype "passive"))
    )
    (net (code "64") (name "Net-(U2-RF1)") (class "Default")
      (node (ref "C14") (pin "1") (pinfunction "1_1") (pintype "passive"))
      (node (ref "C15") (pin "2") (pinfunction "2_2") (pintype "passive"))
      (node (ref "L6") (pin "2") (pinfunction "2_2") (pintype "passive"))
      (node (ref "U2") (pin "1") (pinfunction "RF1_1") (pintype "passive"))
    )
    (net (code "65") (name "Net-(U2-RF2)") (class "Default")
      (node (ref "C19") (pin "1") (pinfunction "1_1") (pintype "passive"))
      (node (ref "U2") (pin "3") (pinfunction "RF2_3") (pintype "passive"))
    )
    (net (code "66") (name "Net-(U2-RFC)") (class "Default")
      (node (ref "C20") (pin "2") (pinfunction "2_2") (pintype "passive"))
      (node (ref "U2") (pin "5") (pinfunction "RFC_5") (pintype "passive"))
    )
    (net (code "67") (name "Net-(U3-A0)") (class "Default")
      (node (ref "R6") (pin "1") (pinfunction "1_1") (pintype "passive"))
      (node (ref "R8") (pin "2") (pinfunction "2_2") (pintype "passive"))
      (node (ref "U3") (pin "1") (pinfunction "A0_1") (pintype "input"))
    )
    (net (code "68") (name "Net-(U3-A1)") (class "Default")
      (node (ref "R7") (pin "1") (pinfunction "1_1") (pintype "passive"))
      (node (ref "R9") (pin "2") (pinfunction "2_2") (pintype "passive"))
      (node (ref "U3") (pin "2") (pinfunction "A1_2") (pintype "input"))
    )
    (net (code "69") (name "Net-(U3-WP)") (class "Default")
      (node (ref "R10") (pin "2") (pinfunction "2_2") (pintype "passive"))
      (node (ref "U3") (pin "7") (pinfunction "WP_7") (pintype "input"))
    )
    (net (code "70") (name "Net-(U4-IN)") (class "Default")
      (node (ref "C19") (pin "2") (pinfunction "2_2") (pintype "passive"))
      (node (ref "U4") (pin "2") (pinfunction "IN_2") (pintype "passive"))
    )
    (net (code "71") (name "Net-(U4-OUT)") (class "Default")
      (node (ref "C18") (pin "1") (pinfunction "1_1") (pintype "passive"))
      (node (ref "U4") (pin "5") (pinfunction "OUT_5") (pintype "passive"))
    )
    (net (code "72") (name "Net-(U5-CTRL)") (class "Default")
      (node (ref "C42") (pin "1") (pinfunction "1_1") (pintype "passive"))
      (node (ref "R15") (pin "1") (pinfunction "1_1") (pintype "passive"))
      (node (ref "U5") (pin "4") (pinfunction "CTRL_4") (pintype "passive"))
    )
    (net (code "73") (name "Net-(U5-RF1)") (class "Default")
      (node (ref "C38") (pin "1") (pinfunction "1_1") (pintype "passive"))
      (node (ref "U5") (pin "1") (pinfunction "RF1_1") (pintype "passive"))
    )
    (net (code "74") (name "Net-(U5-RF2)") (class "Default")
      (node (ref "C33") (pin "1") (pinfunction "1_1") (pintype "passive"))
      (node (ref "C34") (pin "2") (pinfunction "2_2") (pintype "passive"))
      (node (ref "L10") (pin "2") (pinfunction "2_2") (pintype "passive"))
      (node (ref "U5") (pin "3") (pinfunction "RF2_3") (pintype "passive"))
    )
    (net (code "75") (name "Net-(U5-RFC)") (class "Default")
      (node (ref "C39") (pin "2") (pinfunction "2_2") (pintype "passive"))
      (node (ref "U5") (pin "5") (pinfunction "RFC_5") (pintype "passive"))
    )
    (net (code "76") (name "Net-(U6-IN)") (class "Default")
      (node (ref "C38") (pin "2") (pinfunction "2_2") (pintype "passive"))
      (node (ref "U6") (pin "2") (pinfunction "IN_2") (pintype "passive"))
    )
    (net (code "77") (name "Net-(U6-OUT)") (class "Default")
      (node (ref "C36") (pin "1") (pinfunction "1_1") (pintype "passive"))
      (node (ref "U6") (pin "5") (pinfunction "OUT_5") (pintype "passive"))
    )
    (net (code "78") (name "VDD_ANA") (class "Default")
      (node (ref "C24") (pin "2") (pinfunction "2_2") (pintype "passive"))
      (node (ref "C43") (pin "2") (pinfunction "2_2") (pintype "passive"))
      (node (ref "C45") (pin "2") (pinfunction "2_2") (pintype "passive"))
      (node (ref "C6") (pin "2") (pinfunction "2_2") (pintype "passive"))
      (node (ref "K_SX12xx") (pin "22") (pinfunction "22_22") (pintype "passive"))
      (node (ref "R11") (pin "2") (pinfunction "2_2") (pintype "passive"))
      (node (ref "R12") (pin "2") (pinfunction "2_2") (pintype "passive"))
      (node (ref "R6") (pin "2") (pinfunction "2_2") (pintype "passive"))
      (node (ref "R7") (pin "2") (pinfunction "2_2") (pintype "passive"))
      (node (ref "U2") (pin "6") (pinfunction "VDD_6") (pintype "passive"))
      (node (ref "U3") (pin "3") (pinfunction "A2_3") (pintype "input"))
      (node (ref "U3") (pin "8") (pinfunction "VCC_8") (pintype "power_in"))
      (node (ref "U5") (pin "6") (pinfunction "VDD_6") (pintype "passive"))
    )
    (net (code "79") (name "VDD_FEM") (class "Default")
      (node (ref "C25") (pin "1") (pinfunction "1_1") (pintype "passive"))
      (node (ref "K_SX12xx") (pin "34") (pinfunction "34_34") (pintype "passive"))
    )
    (net (code "80") (name "VDD_RF") (class "Default")
      (node (ref "C23") (pin "2") (pinfunction "2_2") (pintype "passive"))
      (node (ref "K_SX12xx") (pin "2") (pinfunction "2_2") (pintype "passive"))
      (node (ref "R3") (pin "2") (pinfunction "2_2") (pintype "passive"))
      (node (ref "VDD_RFS") (pin "1") (pinfunction "1_1") (pintype "passive"))
    )
    (net (code "81") (name "VDD_RFS") (class "Default")
      (node (ref "C21") (pin "2") (pinfunction "2_2") (pintype "passive"))
      (node (ref "C26") (pin "2") (pinfunction "2_2") (pintype "passive"))
      (node (ref "C27") (pin "2") (pinfunction "2_2") (pintype "passive"))
      (node (ref "C3") (pin "2") (pinfunction "2_2") (pintype "passive"))
      (node (ref "C44") (pin "2") (pinfunction "2_2") (pintype "passive"))
      (node (ref "R3") (pin "1") (pinfunction "1_1") (pintype "passive"))
      (node (ref "U1") (pin "14") (pinfunction "VBAT3_14") (pintype "passive"))
      (node (ref "U1") (pin "24") (pinfunction "VBAT2_24") (pintype "passive"))
      (node (ref "U1") (pin "3") (pinfunction "VBAT1_3") (pintype "passive"))
      (node (ref "VDD_RFS") (pin "2") (pinfunction "2_2") (pintype "passive"))
    )
    (net (code "82") (name "unconnected-(K_SX12xx-Pad15)") (class "Default")
      (node (ref "K_SX12xx") (pin "15") (pinfunction "15_15") (pintype "passive+no_connect"))
    )
    (net (code "83") (name "unconnected-(Logo Bot-Pad0)") (class "Default")
      (node (ref "Logo Bot") (pin "0") (pinfunction "0_0") (pintype "passive"))
    )
    (net (code "84") (name "unconnected-(Logo Lora Bot-Pad0)") (class "Default")
      (node (ref "Logo Lora Bot") (pin "0") (pinfunction "0_0") (pintype "passive"))
    )
    (net (code "85") (name "unconnected-(Logo Lora Top-Pad0)") (class "Default")
      (node (ref "Logo Lora Top") (pin "0") (pinfunction "0_0") (pintype "passive"))
    )
    (net (code "86") (name "unconnected-(Logo Top-Pad0)") (class "Default")
      (node (ref "Logo Top") (pin "0") (pinfunction "0_0") (pintype "passive"))
    )
    (net (code "87") (name "unconnected-(R5-Pad1)") (class "Default")
      (node (ref "R5") (pin "1") (pinfunction "1_1") (pintype "passive+no_connect"))
    )
    (net (code "88") (name "unconnected-(R5-Pad8)") (class "Default")
      (node (ref "R5") (pin "8") (pinfunction "8_8") (pintype "passive+no_connect"))
    )
    (net (code "89") (name "unconnected-(U1-RFO_HF-Pad22)") (class "Default")
      (node (ref "U1") (pin "22") (pinfunction "RFO_HF_22") (pintype "passive+no_connect"))
    )
  )
)
